# XMOS_TSBOARD_Power.net
KiCad netlist of a schematic drawn in Altium Designer
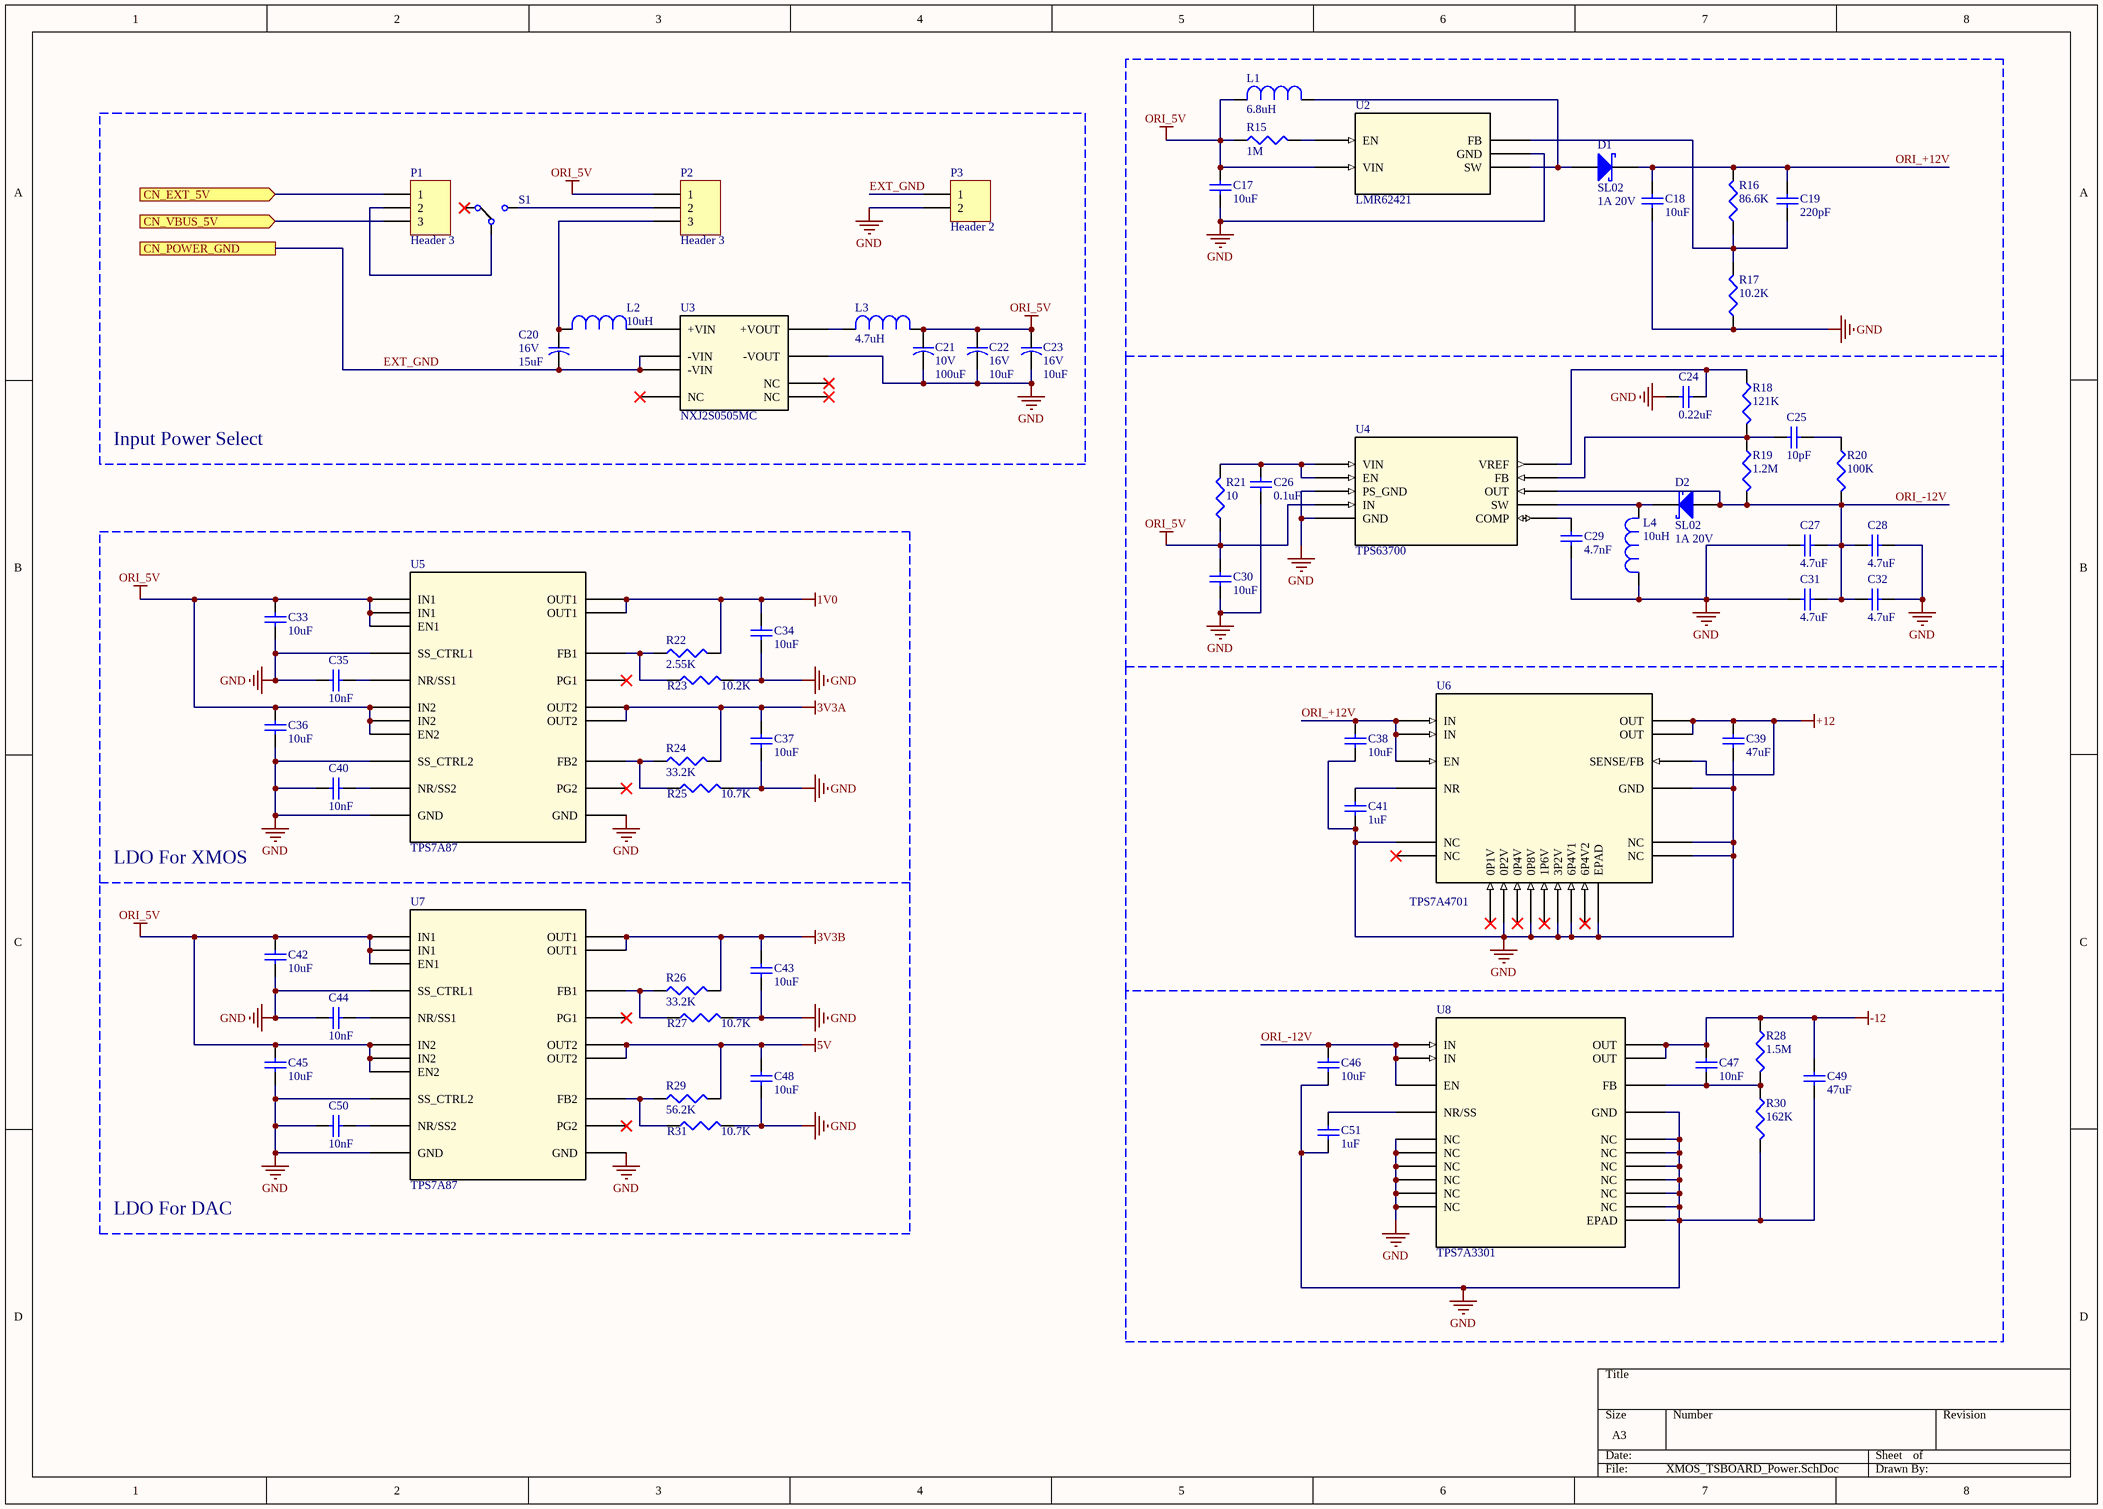
[diagram p0: XMOS_TSBOARD_Power.SchDoc]

(export (version "E")
  (design (tool "Eeschema 10.0.6"))
  (components
    (comp (ref "C17")
      (value "10uF")
      (footprint "1608[0603]")
      (description "Capacitor (Semiconductor SIM Model)")
      (fields (field (name "Comment") "Cap Semi") (field (name "PUBLISHER") "Altium Limited"))
      (libsource (lib "Miscellaneous Devices") (part "Cap Semi"))
    )
    (comp (ref "C18")
      (value "10uF")
      (footprint "C0805")
      (description "Capacitor (Semiconductor SIM Model)")
      (fields (field (name "Comment") "Cap Semi") (field (name "PUBLISHER") "Altium Limited"))
      (libsource (lib "Miscellaneous Devices") (part "Cap Semi"))
    )
    (comp (ref "C19")
      (value "220pF")
      (footprint "1608[0603]")
      (description "Capacitor (Semiconductor SIM Model)")
      (fields (field (name "Comment") "Cap Semi") (field (name "PUBLISHER") "Altium Limited"))
      (libsource (lib "Miscellaneous Devices") (part "Cap Semi"))
    )
    (comp (ref "C20")
      (value "15uF")
      (footprint "3528-21")
      (description "Polymer Electrolytic Capacitors")
      (fields (field (name "RATEDVOLTAGE") "16V") (field (name "Comment") "KO-CAP"))
      (libsource (lib "Troposphere_lib") (part "T520B"))
    )
    (comp (ref "C21")
      (value "100uF")
      (footprint "3528-21")
      (description "Polymer Electrolytic Capacitors")
      (fields (field (name "RATEDVOLTAGE") "10V") (field (name "Comment") "KO-CAP"))
      (libsource (lib "Troposphere_lib") (part "T520B"))
    )
    (comp (ref "C22")
      (value "10uF")
      (footprint "3528-21")
      (description "Polymer Electrolytic Capacitors")
      (fields (field (name "RATEDVOLTAGE") "16V") (field (name "Comment") "KO-CAP"))
      (libsource (lib "Troposphere_lib") (part "T520B"))
    )
    (comp (ref "C23")
      (value "10uF")
      (footprint "3528-21")
      (description "Polymer Electrolytic Capacitors")
      (fields (field (name "RATEDVOLTAGE") "16V") (field (name "Comment") "KO-CAP"))
      (libsource (lib "Troposphere_lib") (part "T520B"))
    )
    (comp (ref "C24")
      (value "0.22uF")
      (footprint "1608[0603]")
      (description "Capacitor (Semiconductor SIM Model)")
      (fields (field (name "Comment") "Cap Semi") (field (name "PUBLISHER") "Altium Limited"))
      (libsource (lib "Miscellaneous Devices") (part "Cap Semi"))
    )
    (comp (ref "C25")
      (value "10pF")
      (footprint "1608[0603]")
      (description "Capacitor (Semiconductor SIM Model)")
      (fields (field (name "Comment") "Cap Semi") (field (name "PUBLISHER") "Altium Limited"))
      (libsource (lib "Miscellaneous Devices") (part "Cap Semi"))
    )
    (comp (ref "C26")
      (value "0.1uF")
      (footprint "1608[0603]")
      (description "Capacitor (Semiconductor SIM Model)")
      (fields (field (name "Comment") "Cap Semi") (field (name "PUBLISHER") "Altium Limited"))
      (libsource (lib "Miscellaneous Devices") (part "Cap Semi"))
    )
    (comp (ref "C27")
      (value "4.7uF")
      (footprint "C0805")
      (description "Capacitor (Semiconductor SIM Model)")
      (fields (field (name "Comment") "Cap Semi") (field (name "PUBLISHER") "Altium Limited"))
      (libsource (lib "Miscellaneous Devices") (part "Cap Semi"))
    )
    (comp (ref "C28")
      (value "4.7uF")
      (footprint "C0805")
      (description "Capacitor (Semiconductor SIM Model)")
      (fields (field (name "Comment") "Cap Semi") (field (name "PUBLISHER") "Altium Limited"))
      (libsource (lib "Miscellaneous Devices") (part "Cap Semi"))
    )
    (comp (ref "C29")
      (value "4.7nF")
      (footprint "1608[0603]")
      (description "Capacitor (Semiconductor SIM Model)")
      (fields (field (name "Comment") "Cap Semi") (field (name "PUBLISHER") "Altium Limited"))
      (libsource (lib "Miscellaneous Devices") (part "Cap Semi"))
    )
    (comp (ref "C30")
      (value "10uF")
      (footprint "1608[0603]")
      (description "Capacitor (Semiconductor SIM Model)")
      (fields (field (name "Comment") "Cap Semi") (field (name "PUBLISHER") "Altium Limited"))
      (libsource (lib "Miscellaneous Devices") (part "Cap Semi"))
    )
    (comp (ref "C31")
      (value "4.7uF")
      (footprint "C0805")
      (description "Capacitor (Semiconductor SIM Model)")
      (fields (field (name "Comment") "Cap Semi") (field (name "PUBLISHER") "Altium Limited"))
      (libsource (lib "Miscellaneous Devices") (part "Cap Semi"))
    )
    (comp (ref "C32")
      (value "4.7uF")
      (footprint "C0805")
      (description "Capacitor (Semiconductor SIM Model)")
      (fields (field (name "Comment") "Cap Semi") (field (name "PUBLISHER") "Altium Limited"))
      (libsource (lib "Miscellaneous Devices") (part "Cap Semi"))
    )
    (comp (ref "C33")
      (value "10uF")
      (footprint "1608[0603]")
      (description "Capacitor (Semiconductor SIM Model)")
      (fields (field (name "Comment") "Cap Semi") (field (name "PUBLISHER") "Altium Limited"))
      (libsource (lib "Miscellaneous Devices") (part "Cap Semi"))
    )
    (comp (ref "C34")
      (value "10uF")
      (footprint "1608[0603]")
      (description "Capacitor (Semiconductor SIM Model)")
      (fields (field (name "Comment") "Cap Semi") (field (name "PUBLISHER") "Altium Limited"))
      (libsource (lib "Miscellaneous Devices") (part "Cap Semi"))
    )
    (comp (ref "C35")
      (value "10nF")
      (footprint "1608[0603]")
      (description "Capacitor (Semiconductor SIM Model)")
      (fields (field (name "Comment") "Cap Semi") (field (name "PUBLISHER") "Altium Limited"))
      (libsource (lib "Miscellaneous Devices") (part "Cap Semi"))
    )
    (comp (ref "C36")
      (value "10uF")
      (footprint "1608[0603]")
      (description "Capacitor (Semiconductor SIM Model)")
      (fields (field (name "Comment") "Cap Semi") (field (name "PUBLISHER") "Altium Limited"))
      (libsource (lib "Miscellaneous Devices") (part "Cap Semi"))
    )
    (comp (ref "C37")
      (value "10uF")
      (footprint "1608[0603]")
      (description "Capacitor (Semiconductor SIM Model)")
      (fields (field (name "Comment") "Cap Semi") (field (name "PUBLISHER") "Altium Limited"))
      (libsource (lib "Miscellaneous Devices") (part "Cap Semi"))
    )
    (comp (ref "C38")
      (value "10uF")
      (footprint "C0805")
      (description "Capacitor (Semiconductor SIM Model)")
      (fields (field (name "Comment") "Cap Semi") (field (name "PUBLISHER") "Altium Limited"))
      (libsource (lib "Miscellaneous Devices") (part "Cap Semi"))
    )
    (comp (ref "C39")
      (value "47uF")
      (footprint "C1210")
      (description "Capacitor (Semiconductor SIM Model)")
      (fields (field (name "Comment") "Cap Semi") (field (name "PUBLISHER") "Altium Limited"))
      (libsource (lib "Miscellaneous Devices") (part "Cap Semi"))
    )
    (comp (ref "C40")
      (value "10nF")
      (footprint "1608[0603]")
      (description "Capacitor (Semiconductor SIM Model)")
      (fields (field (name "Comment") "Cap Semi") (field (name "PUBLISHER") "Altium Limited"))
      (libsource (lib "Miscellaneous Devices") (part "Cap Semi"))
    )
    (comp (ref "C41")
      (value "1uF")
      (footprint "1608[0603]")
      (description "Capacitor (Semiconductor SIM Model)")
      (fields (field (name "Comment") "Cap Semi") (field (name "PUBLISHER") "Altium Limited"))
      (libsource (lib "Miscellaneous Devices") (part "Cap Semi"))
    )
    (comp (ref "C42")
      (value "10uF")
      (footprint "1608[0603]")
      (description "Capacitor (Semiconductor SIM Model)")
      (fields (field (name "Comment") "Cap Semi") (field (name "PUBLISHER") "Altium Limited"))
      (libsource (lib "Miscellaneous Devices") (part "Cap Semi"))
    )
    (comp (ref "C43")
      (value "10uF")
      (footprint "1608[0603]")
      (description "Capacitor (Semiconductor SIM Model)")
      (fields (field (name "Comment") "Cap Semi") (field (name "PUBLISHER") "Altium Limited"))
      (libsource (lib "Miscellaneous Devices") (part "Cap Semi"))
    )
    (comp (ref "C44")
      (value "10nF")
      (footprint "1608[0603]")
      (description "Capacitor (Semiconductor SIM Model)")
      (fields (field (name "Comment") "Cap Semi") (field (name "PUBLISHER") "Altium Limited"))
      (libsource (lib "Miscellaneous Devices") (part "Cap Semi"))
    )
    (comp (ref "C45")
      (value "10uF")
      (footprint "1608[0603]")
      (description "Capacitor (Semiconductor SIM Model)")
      (fields (field (name "Comment") "Cap Semi") (field (name "PUBLISHER") "Altium Limited"))
      (libsource (lib "Miscellaneous Devices") (part "Cap Semi"))
    )
    (comp (ref "C46")
      (value "10uF")
      (footprint "C0805")
      (description "Capacitor (Semiconductor SIM Model)")
      (fields (field (name "Comment") "Cap Semi") (field (name "PUBLISHER") "Altium Limited"))
      (libsource (lib "Miscellaneous Devices") (part "Cap Semi"))
    )
    (comp (ref "C47")
      (value "10nF")
      (footprint "1608[0603]")
      (description "Capacitor (Semiconductor SIM Model)")
      (fields (field (name "Comment") "Cap Semi") (field (name "PUBLISHER") "Altium Limited"))
      (libsource (lib "Miscellaneous Devices") (part "Cap Semi"))
    )
    (comp (ref "C48")
      (value "10uF")
      (footprint "1608[0603]")
      (description "Capacitor (Semiconductor SIM Model)")
      (fields (field (name "Comment") "Cap Semi") (field (name "PUBLISHER") "Altium Limited"))
      (libsource (lib "Miscellaneous Devices") (part "Cap Semi"))
    )
    (comp (ref "C49")
      (value "47uF")
      (footprint "C1210")
      (description "Capacitor (Semiconductor SIM Model)")
      (fields (field (name "Comment") "Cap Semi") (field (name "PUBLISHER") "Altium Limited"))
      (libsource (lib "Miscellaneous Devices") (part "Cap Semi"))
    )
    (comp (ref "C50")
      (value "10nF")
      (footprint "1608[0603]")
      (description "Capacitor (Semiconductor SIM Model)")
      (fields (field (name "Comment") "Cap Semi") (field (name "PUBLISHER") "Altium Limited"))
      (libsource (lib "Miscellaneous Devices") (part "Cap Semi"))
    )
    (comp (ref "C51")
      (value "1uF")
      (footprint "1608[0603]")
      (description "Capacitor (Semiconductor SIM Model)")
      (fields (field (name "Comment") "Cap Semi") (field (name "PUBLISHER") "Altium Limited"))
      (libsource (lib "Miscellaneous Devices") (part "Cap Semi"))
    )
    (comp (ref "D1")
      (value "SL02")
      (footprint "DO-219AB")
      (description "Schottky Rectifier")
      (fields (field (name "ALTIUM_VALUE") "1A 20V"))
      (libsource (lib "Troposphere_lib") (part "SL02"))
    )
    (comp (ref "D2")
      (value "SL02")
      (footprint "DO-219AB")
      (description "Schottky Rectifier")
      (fields (field (name "ALTIUM_VALUE") "1A 20V"))
      (libsource (lib "Troposphere_lib") (part "SL02"))
    )
    (comp (ref "L1")
      (value "6.8uH")
      (footprint "4240")
      (description "Inductors for power circuits, wound metal, SPM series")
      (fields (field (name "Comment") "SPM"))
      (libsource (lib "Troposphere_lib") (part "SPM"))
    )
    (comp (ref "L2")
      (value "10uH")
      (footprint "5250")
      (description "Inductors for power circuits, wound metal, SPM series")
      (fields (field (name "Comment") "SPM"))
      (libsource (lib "Troposphere_lib") (part "SPM"))
    )
    (comp (ref "L3")
      (value "4.7uH")
      (footprint "4240")
      (description "Inductors for power circuits, wound metal, SPM series")
      (fields (field (name "Comment") "SPM"))
      (libsource (lib "Troposphere_lib") (part "SPM"))
    )
    (comp (ref "L4")
      (value "10uH")
      (footprint "4240")
      (description "Inductors for power circuits, wound metal, SPM series")
      (fields (field (name "Comment") "SPM"))
      (libsource (lib "Troposphere_lib") (part "SPM"))
    )
    (comp (ref "P1")
      (value "Header 3")
      (footprint "HDR1X3")
      (description "Header, 3-Pin")
      (fields (field (name "PUBLISHER") "Altium Limited"))
      (libsource (lib "Miscellaneous Connectors") (part "Header 3"))
    )
    (comp (ref "P2")
      (value "Header 3")
      (footprint "HDR1X3")
      (description "Header, 3-Pin")
      (fields (field (name "PUBLISHER") "Altium Limited"))
      (libsource (lib "Miscellaneous Connectors") (part "Header 3"))
    )
    (comp (ref "P3")
      (value "Header 2")
      (footprint "HDR1X2")
      (description "Header, 2-Pin")
      (fields (field (name "PUBLISHER") "Altium Limited"))
      (libsource (lib "Miscellaneous Connectors") (part "Header 2"))
    )
    (comp (ref "R15")
      (value "1M")
      (footprint "J1-0603")
      (description "Resistor")
      (fields (field (name "Comment") "Res3") (field (name "PUBLISHER") "Altium Limited"))
      (libsource (lib "Miscellaneous Devices") (part "Res3"))
    )
    (comp (ref "R16")
      (value "86.6K")
      (footprint "J1-0603")
      (description "Resistor")
      (fields (field (name "Comment") "Res3") (field (name "PUBLISHER") "Altium Limited"))
      (libsource (lib "Miscellaneous Devices") (part "Res3"))
    )
    (comp (ref "R17")
      (value "10.2K")
      (footprint "J1-0603")
      (description "Resistor")
      (fields (field (name "Comment") "Res3") (field (name "PUBLISHER") "Altium Limited"))
      (libsource (lib "Miscellaneous Devices") (part "Res3"))
    )
    (comp (ref "R18")
      (value "121K")
      (footprint "J1-0603")
      (description "Resistor")
      (fields (field (name "Comment") "Res3") (field (name "PUBLISHER") "Altium Limited"))
      (libsource (lib "Miscellaneous Devices") (part "Res3"))
    )
    (comp (ref "R19")
      (value "1.2M")
      (footprint "J1-0603")
      (description "Resistor")
      (fields (field (name "Comment") "Res3") (field (name "PUBLISHER") "Altium Limited"))
      (libsource (lib "Miscellaneous Devices") (part "Res3"))
    )
    (comp (ref "R20")
      (value "100K")
      (footprint "J1-0603")
      (description "Resistor")
      (fields (field (name "Comment") "Res3") (field (name "PUBLISHER") "Altium Limited"))
      (libsource (lib "Miscellaneous Devices") (part "Res3"))
    )
    (comp (ref "R21")
      (value "10")
      (footprint "J1-0603")
      (description "Resistor")
      (fields (field (name "Comment") "Res3") (field (name "PUBLISHER") "Altium Limited"))
      (libsource (lib "Miscellaneous Devices") (part "Res3"))
    )
    (comp (ref "R22")
      (value "2.55K")
      (footprint "J1-0603")
      (description "Resistor")
      (fields (field (name "Comment") "Res3") (field (name "PUBLISHER") "Altium Limited"))
      (libsource (lib "Miscellaneous Devices") (part "Res3"))
    )
    (comp (ref "R23")
      (value "10.2K")
      (footprint "J1-0603")
      (description "Resistor")
      (fields (field (name "Comment") "Res3") (field (name "PUBLISHER") "Altium Limited"))
      (libsource (lib "Miscellaneous Devices") (part "Res3"))
    )
    (comp (ref "R24")
      (value "33.2K")
      (footprint "J1-0603")
      (description "Resistor")
      (fields (field (name "Comment") "Res3") (field (name "PUBLISHER") "Altium Limited"))
      (libsource (lib "Miscellaneous Devices") (part "Res3"))
    )
    (comp (ref "R25")
      (value "10.7K")
      (footprint "J1-0603")
      (description "Resistor")
      (fields (field (name "Comment") "Res3") (field (name "PUBLISHER") "Altium Limited"))
      (libsource (lib "Miscellaneous Devices") (part "Res3"))
    )
    (comp (ref "R26")
      (value "33.2K")
      (footprint "J1-0603")
      (description "Resistor")
      (fields (field (name "Comment") "Res3") (field (name "PUBLISHER") "Altium Limited"))
      (libsource (lib "Miscellaneous Devices") (part "Res3"))
    )
    (comp (ref "R27")
      (value "10.7K")
      (footprint "J1-0603")
      (description "Resistor")
      (fields (field (name "Comment") "Res3") (field (name "PUBLISHER") "Altium Limited"))
      (libsource (lib "Miscellaneous Devices") (part "Res3"))
    )
    (comp (ref "R28")
      (value "1.5M")
      (footprint "J1-0603")
      (description "Resistor")
      (fields (field (name "Comment") "Res3") (field (name "PUBLISHER") "Altium Limited"))
      (libsource (lib "Miscellaneous Devices") (part "Res3"))
    )
    (comp (ref "R29")
      (value "56.2K")
      (footprint "J1-0603")
      (description "Resistor")
      (fields (field (name "Comment") "Res3") (field (name "PUBLISHER") "Altium Limited"))
      (libsource (lib "Miscellaneous Devices") (part "Res3"))
    )
    (comp (ref "R30")
      (value "162K")
      (footprint "J1-0603")
      (description "Resistor")
      (fields (field (name "Comment") "Res3") (field (name "PUBLISHER") "Altium Limited"))
      (libsource (lib "Miscellaneous Devices") (part "Res3"))
    )
    (comp (ref "R31")
      (value "10.7K")
      (footprint "J1-0603")
      (description "Resistor")
      (fields (field (name "Comment") "Res3") (field (name "PUBLISHER") "Altium Limited"))
      (libsource (lib "Miscellaneous Devices") (part "Res3"))
    )
    (comp (ref "S1")
      (value "SSSS213202")
      (footprint "SS_SMD_213202")
      (description "Slide Switch 3.5(H)mm, 2.0mm-travel Type SSSS2 Series")
      (libsource (lib "Troposphere_lib") (part "SSSS213202"))
    )
    (comp (ref "U2")
      (value "LMR62421")
      (footprint "DBV5")
      (description "LMR62421 SIMPLE SWITCHER® 24Vout, 2.1A Step-Up Voltage Regulator in SOT-23")
      (libsource (lib "Troposphere_lib") (part "LMR62421"))
    )
    (comp (ref "U3")
      (value "NXJ2S0505MC")
      (footprint "SMD_NXJ2S0505")
      (description "Isolated 2W Single Output SM DC-DC Converters")
      (libsource (lib "Troposphere_lib") (part "NXJ2S0505MC"))
    )
    (comp (ref "U4")
      (value "TPS63700")
      (footprint "DRC10")
      (description "DC-DC Inverter")
      (libsource (lib "Troposphere_lib") (part "TPS63700"))
    )
    (comp (ref "U5")
      (value "TPS7A87")
      (footprint "RTJ20")
      (description "Dual, 500-mA, Low-Noise (3.8 μVRMS), LDO Voltage Regulator")
      (libsource (lib "Troposphere_lib") (part "TPS7A87"))
    )
    (comp (ref "U6")
      (value "TPS7A4701")
      (footprint "RGW20")
      (description "TPS7A470x 36-V, 1-A, 4-µVRMS, RF LDO Voltage Regulator")
      (libsource (lib "Troposphere_lib") (part "TPS7A4701"))
    )
    (comp (ref "U7")
      (value "TPS7A87")
      (footprint "RTJ20")
      (description "Dual, 500-mA, Low-Noise (3.8 μVRMS), LDO Voltage Regulator")
      (libsource (lib "Troposphere_lib") (part "TPS7A87"))
    )
    (comp (ref "U8")
      (value "TPS7A3301")
      (footprint "RGW20")
      (description "TPS7A33 –36-V, 1-A, Ultralow-Noise Negative Voltage Regulator")
      (libsource (lib "Troposphere_lib") (part "TPS7A3301"))
    )
  )
  (nets
    (net (code "1") (name "+12") (class "Default")
      (node (ref "C39") (pin "2") (pinfunction "2_2") (pintype "passive"))
      (node (ref "U6") (pin "1") (pinfunction "OUT_1") (pintype "power_in"))
      (node (ref "U6") (pin "20") (pinfunction "OUT_20") (pintype "power_in"))
      (node (ref "U6") (pin "3") (pinfunction "SENSE/FB_3") (pintype "input"))
    )
    (net (code "2") (name "-12") (class "Default")
      (node (ref "C47") (pin "1") (pinfunction "1_1") (pintype "passive"))
      (node (ref "C49") (pin "2") (pinfunction "2_2") (pintype "passive"))
      (node (ref "R28") (pin "1") (pinfunction "1_1") (pintype "passive"))
      (node (ref "U8") (pin "1") (pinfunction "OUT_1") (pintype "power_in"))
      (node (ref "U8") (pin "20") (pinfunction "OUT_20") (pintype "power_in"))
    )
    (net (code "3") (name "/CN_EXT_5V") (class "Default")
      (node (ref "P1") (pin "1") (pinfunction "1_1") (pintype "passive"))
    )
    (net (code "4") (name "/CN_VBUS_5V") (class "Default")
      (node (ref "P1") (pin "3") (pinfunction "3_3") (pintype "passive"))
    )
    (net (code "5") (name "/EXT_GND") (class "Default")
      (node (ref "C20") (pin "2") (pinfunction "2_2") (pintype "passive"))
      (node (ref "P3") (pin "1") (pinfunction "1_1") (pintype "passive"))
      (node (ref "U3") (pin "11") (pinfunction "-VIN_11") (pintype "power_in"))
      (node (ref "U3") (pin "2") (pinfunction "-VIN_2") (pintype "power_in"))
    )
    (net (code "6") (name "/ORI_+12V") (class "Default")
      (node (ref "C18") (pin "2") (pinfunction "2_2") (pintype "passive"))
      (node (ref "C19") (pin "2") (pinfunction "2_2") (pintype "passive"))
      (node (ref "C38") (pin "2") (pinfunction "2_2") (pintype "passive"))
      (node (ref "D1") (pin "2") (pinfunction "2_2") (pintype "power_in"))
      (node (ref "R16") (pin "2") (pinfunction "2_2") (pintype "passive"))
      (node (ref "U6") (pin "13") (pinfunction "EN_13") (pintype "input"))
      (node (ref "U6") (pin "15") (pinfunction "IN_15") (pintype "input"))
      (node (ref "U6") (pin "16") (pinfunction "IN_16") (pintype "input"))
    )
    (net (code "7") (name "/ORI_-12V") (class "Default")
      (node (ref "C27") (pin "1") (pinfunction "1_1") (pintype "passive"))
      (node (ref "C28") (pin "2") (pinfunction "2_2") (pintype "passive"))
      (node (ref "C31") (pin "1") (pinfunction "1_1") (pintype "passive"))
      (node (ref "C32") (pin "2") (pinfunction "2_2") (pintype "passive"))
      (node (ref "C46") (pin "2") (pinfunction "2_2") (pintype "passive"))
      (node (ref "D2") (pin "1") (pinfunction "1_1") (pintype "power_in"))
      (node (ref "R19") (pin "2") (pinfunction "2_2") (pintype "passive"))
      (node (ref "R20") (pin "2") (pinfunction "2_2") (pintype "passive"))
      (node (ref "U4") (pin "8") (pinfunction "OUT_8") (pintype "input"))
      (node (ref "U8") (pin "13") (pinfunction "EN_13") (pintype "passive"))
      (node (ref "U8") (pin "15") (pinfunction "IN_15") (pintype "input"))
      (node (ref "U8") (pin "16") (pinfunction "IN_16") (pintype "input"))
    )
    (net (code "8") (name "1V0") (class "Default")
      (node (ref "C34") (pin "2") (pinfunction "2_2") (pintype "passive"))
      (node (ref "R22") (pin "2") (pinfunction "2_2") (pintype "passive"))
      (node (ref "U5") (pin "14") (pinfunction "OUT1_14") (pintype "power_in"))
      (node (ref "U5") (pin "15") (pinfunction "OUT1_15") (pintype "power_in"))
    )
    (net (code "9") (name "3V3A") (class "Default")
      (node (ref "C37") (pin "2") (pinfunction "2_2") (pintype "passive"))
      (node (ref "R24") (pin "2") (pinfunction "2_2") (pintype "passive"))
      (node (ref "U5") (pin "11") (pinfunction "OUT2_11") (pintype "power_in"))
      (node (ref "U5") (pin "12") (pinfunction "OUT2_12") (pintype "power_in"))
    )
    (net (code "10") (name "3V3B") (class "Default")
      (node (ref "C43") (pin "2") (pinfunction "2_2") (pintype "passive"))
      (node (ref "R26") (pin "2") (pinfunction "2_2") (pintype "passive"))
      (node (ref "U7") (pin "14") (pinfunction "OUT1_14") (pintype "power_in"))
      (node (ref "U7") (pin "15") (pinfunction "OUT1_15") (pintype "power_in"))
    )
    (net (code "11") (name "5V") (class "Default")
      (node (ref "C48") (pin "2") (pinfunction "2_2") (pintype "passive"))
      (node (ref "R29") (pin "2") (pinfunction "2_2") (pintype "passive"))
      (node (ref "U7") (pin "11") (pinfunction "OUT2_11") (pintype "power_in"))
      (node (ref "U7") (pin "12") (pinfunction "OUT2_12") (pintype "power_in"))
    )
    (net (code "12") (name "GND") (class "Default")
      (node (ref "C17") (pin "1") (pinfunction "1_1") (pintype "passive"))
      (node (ref "C18") (pin "1") (pinfunction "1_1") (pintype "passive"))
      (node (ref "C21") (pin "2") (pinfunction "2_2") (pintype "passive"))
      (node (ref "C22") (pin "2") (pinfunction "2_2") (pintype "passive"))
      (node (ref "C23") (pin "2") (pinfunction "2_2") (pintype "passive"))
      (node (ref "C24") (pin "2") (pinfunction "2_2") (pintype "passive"))
      (node (ref "C26") (pin "1") (pinfunction "1_1") (pintype "passive"))
      (node (ref "C27") (pin "2") (pinfunction "2_2") (pintype "passive"))
      (node (ref "C28") (pin "1") (pinfunction "1_1") (pintype "passive"))
      (node (ref "C29") (pin "2") (pinfunction "2_2") (pintype "passive"))
      (node (ref "C30") (pin "1") (pinfunction "1_1") (pintype "passive"))
      (node (ref "C31") (pin "2") (pinfunction "2_2") (pintype "passive"))
      (node (ref "C32") (pin "1") (pinfunction "1_1") (pintype "passive"))
      (node (ref "C33") (pin "1") (pinfunction "1_1") (pintype "passive"))
      (node (ref "C34") (pin "1") (pinfunction "1_1") (pintype "passive"))
      (node (ref "C35") (pin "1") (pinfunction "1_1") (pintype "passive"))
      (node (ref "C36") (pin "1") (pinfunction "1_1") (pintype "passive"))
      (node (ref "C37") (pin "1") (pinfunction "1_1") (pintype "passive"))
      (node (ref "C38") (pin "1") (pinfunction "1_1") (pintype "passive"))
      (node (ref "C39") (pin "1") (pinfunction "1_1") (pintype "passive"))
      (node (ref "C40") (pin "1") (pinfunction "1_1") (pintype "passive"))
      (node (ref "C41") (pin "1") (pinfunction "1_1") (pintype "passive"))
      (node (ref "C42") (pin "1") (pinfunction "1_1") (pintype "passive"))
      (node (ref "C43") (pin "1") (pinfunction "1_1") (pintype "passive"))
      (node (ref "C44") (pin "1") (pinfunction "1_1") (pintype "passive"))
      (node (ref "C45") (pin "1") (pinfunction "1_1") (pintype "passive"))
      (node (ref "C46") (pin "1") (pinfunction "1_1") (pintype "passive"))
      (node (ref "C48") (pin "1") (pinfunction "1_1") (pintype "passive"))
      (node (ref "C49") (pin "1") (pinfunction "1_1") (pintype "passive"))
      (node (ref "C50") (pin "1") (pinfunction "1_1") (pintype "passive"))
      (node (ref "C51") (pin "1") (pinfunction "1_1") (pintype "passive"))
      (node (ref "L4") (pin "2") (pinfunction "2_2") (pintype "passive"))
      (node (ref "P3") (pin "2") (pinfunction "2_2") (pintype "passive"))
      (node (ref "R17") (pin "1") (pinfunction "1_1") (pintype "passive"))
      (node (ref "R23") (pin "2") (pinfunction "2_2") (pintype "passive"))
      (node (ref "R25") (pin "2") (pinfunction "2_2") (pintype "passive"))
      (node (ref "R27") (pin "2") (pinfunction "2_2") (pintype "passive"))
      (node (ref "R30") (pin "2") (pinfunction "2_2") (pintype "passive"))
      (node (ref "R31") (pin "2") (pinfunction "2_2") (pintype "passive"))
      (node (ref "U2") (pin "2") (pinfunction "GND_2") (pintype "power_in"))
      (node (ref "U3") (pin "5") (pinfunction "-VOUT_5") (pintype "power_in"))
      (node (ref "U4") (pin "2") (pinfunction "GND_2") (pintype "power_in"))
      (node (ref "U4") (pin "7") (pinfunction "PS_GND_7") (pintype "input"))
      (node (ref "U5") (pin "13") (pinfunction "GND_13") (pintype "power_in"))
      (node (ref "U5") (pin "18") (pinfunction "SS_CTRL1_18") (pintype "power_in"))
      (node (ref "U5") (pin "3") (pinfunction "GND_3") (pintype "power_in"))
      (node (ref "U5") (pin "8") (pinfunction "SS_CTRL2_8") (pintype "power_in"))
      (node (ref "U6") (pin "11") (pinfunction "0P2V_11") (pintype "input"))
      (node (ref "U6") (pin "17") (pinfunction "NC_17") (pintype "passive"))
      (node (ref "U6") (pin "18") (pinfunction "NC_18") (pintype "passive"))
      (node (ref "U6") (pin "19") (pinfunction "NC_19") (pintype "passive"))
      (node (ref "U6") (pin "21") (pinfunction "EPAD_21") (pintype "passive"))
      (node (ref "U6") (pin "5") (pinfunction "6P4V1_5") (pintype "input"))
      (node (ref "U6") (pin "6") (pinfunction "3P2V_6") (pintype "input"))
      (node (ref "U6") (pin "7") (pinfunction "GND_7") (pintype "power_in"))
      (node (ref "U6") (pin "9") (pinfunction "0P8V_9") (pintype "input"))
      (node (ref "U7") (pin "13") (pinfunction "GND_13") (pintype "power_in"))
      (node (ref "U7") (pin "18") (pinfunction "SS_CTRL1_18") (pintype "power_in"))
      (node (ref "U7") (pin "3") (pinfunction "GND_3") (pintype "power_in"))
      (node (ref "U7") (pin "8") (pinfunction "SS_CTRL2_8") (pintype "power_in"))
      (node (ref "U8") (pin "10") (pinfunction "NC_10") (pintype "passive"))
      (node (ref "U8") (pin "11") (pinfunction "NC_11") (pintype "passive"))
      (node (ref "U8") (pin "12") (pinfunction "NC_12") (pintype "passive"))
      (node (ref "U8") (pin "17") (pinfunction "NC_17") (pintype "passive"))
      (node (ref "U8") (pin "18") (pinfunction "NC_18") (pintype "passive"))
      (node (ref "U8") (pin "19") (pinfunction "NC_19") (pintype "passive"))
      (node (ref "U8") (pin "2") (pinfunction "NC_2") (pintype "passive"))
      (node (ref "U8") (pin "21") (pinfunction "EPAD_21") (pintype "passive"))
      (node (ref "U8") (pin "4") (pinfunction "NC_4") (pintype "passive"))
      (node (ref "U8") (pin "5") (pinfunction "NC_5") (pintype "passive"))
      (node (ref "U8") (pin "6") (pinfunction "NC_6") (pintype "passive"))
      (node (ref "U8") (pin "7") (pinfunction "GND_7") (pintype "power_in"))
      (node (ref "U8") (pin "8") (pinfunction "NC_8") (pintype "passive"))
      (node (ref "U8") (pin "9") (pinfunction "NC_9") (pintype "passive"))
    )
    (net (code "13") (name "Net-(C20-Pad1)") (class "Default")
      (node (ref "C20") (pin "1") (pinfunction "1_1") (pintype "passive"))
      (node (ref "L2") (pin "2") (pinfunction "2_2") (pintype "passive"))
      (node (ref "P2") (pin "3") (pinfunction "3_3") (pintype "passive"))
    )
    (net (code "14") (name "Net-(C25-Pad1)") (class "Default")
      (node (ref "C25") (pin "1") (pinfunction "1_1") (pintype "passive"))
      (node (ref "R20") (pin "1") (pinfunction "1_1") (pintype "passive"))
    )
    (net (code "15") (name "Net-(P2-Pad2)") (class "Default")
      (node (ref "P2") (pin "2") (pinfunction "2_2") (pintype "passive"))
      (node (ref "S1") (pin "3") (pinfunction "3_3") (pintype "power_in"))
    )
    (net (code "16") (name "Net-(S1-COM)") (class "Default")
      (node (ref "P1") (pin "2") (pinfunction "2_2") (pintype "passive"))
      (node (ref "S1") (pin "2") (pinfunction "COM_2") (pintype "power_in"))
    )
    (net (code "17") (name "Net-(U2-EN)") (class "Default")
      (node (ref "R15") (pin "2") (pinfunction "2_2") (pintype "passive"))
      (node (ref "U2") (pin "4") (pinfunction "EN_4") (pintype "input"))
    )
    (net (code "18") (name "Net-(U2-FB)") (class "Default")
      (node (ref "C19") (pin "1") (pinfunction "1_1") (pintype "passive"))
      (node (ref "R16") (pin "1") (pinfunction "1_1") (pintype "passive"))
      (node (ref "R17") (pin "2") (pinfunction "2_2") (pintype "passive"))
      (node (ref "U2") (pin "3") (pinfunction "FB_3") (pintype "passive"))
    )
    (net (code "19") (name "Net-(U2-SW)") (class "Default")
      (node (ref "D1") (pin "1") (pinfunction "1_1") (pintype "power_in"))
      (node (ref "L1") (pin "1") (pinfunction "1_1") (pintype "passive"))
      (node (ref "U2") (pin "1") (pinfunction "SW_1") (pintype "power_in"))
    )
    (net (code "20") (name "Net-(U3-+VIN)") (class "Default")
      (node (ref "L2") (pin "1") (pinfunction "1_1") (pintype "passive"))
      (node (ref "U3") (pin "1") (pinfunction "+VIN_1") (pintype "power_in"))
    )
    (net (code "21") (name "Net-(U3-+VOUT)") (class "Default")
      (node (ref "L3") (pin "2") (pinfunction "2_2") (pintype "passive"))
      (node (ref "U3") (pin "6") (pinfunction "+VOUT_6") (pintype "power_in"))
    )
    (net (code "22") (name "Net-(U4-COMP)") (class "Default")
      (node (ref "C29") (pin "1") (pinfunction "1_1") (pintype "passive"))
      (node (ref "U4") (pin "1") (pinfunction "COMP_1") (pintype "bidirectional"))
    )
    (net (code "23") (name "Net-(U4-EN)") (class "Default")
      (node (ref "C26") (pin "2") (pinfunction "2_2") (pintype "passive"))
      (node (ref "R21") (pin "2") (pinfunction "2_2") (pintype "passive"))
      (node (ref "U4") (pin "3") (pinfunction "VIN_3") (pintype "input"))
      (node (ref "U4") (pin "4") (pinfunction "EN_4") (pintype "input"))
    )
    (net (code "24") (name "Net-(U4-FB)") (class "Default")
      (node (ref "C25") (pin "2") (pinfunction "2_2") (pintype "passive"))
      (node (ref "R18") (pin "2") (pinfunction "2_2") (pintype "passive"))
      (node (ref "R19") (pin "1") (pinfunction "1_1") (pintype "passive"))
      (node (ref "U4") (pin "9") (pinfunction "FB_9") (pintype "input"))
    )
    (net (code "25") (name "Net-(U4-SW)") (class "Default")
      (node (ref "D2") (pin "2") (pinfunction "2_2") (pintype "power_in"))
      (node (ref "L4") (pin "1") (pinfunction "1_1") (pintype "passive"))
      (node (ref "U4") (pin "6") (pinfunction "SW_6") (pintype "power_in"))
    )
    (net (code "26") (name "Net-(U4-VREF)") (class "Default")
      (node (ref "C24") (pin "1") (pinfunction "1_1") (pintype "passive"))
      (node (ref "R18") (pin "1") (pinfunction "1_1") (pintype "passive"))
      (node (ref "U4") (pin "10") (pinfunction "VREF_10") (pintype "output"))
    )
    (net (code "27") (name "Net-(U5-FB1)") (class "Default")
      (node (ref "R22") (pin "1") (pinfunction "1_1") (pintype "passive"))
      (node (ref "R23") (pin "1") (pinfunction "1_1") (pintype "passive"))
      (node (ref "U5") (pin "16") (pinfunction "FB1_16") (pintype "power_in"))
    )
    (net (code "28") (name "Net-(U5-FB2)") (class "Default")
      (node (ref "R24") (pin "1") (pinfunction "1_1") (pintype "passive"))
      (node (ref "R25") (pin "1") (pinfunction "1_1") (pintype "passive"))
      (node (ref "U5") (pin "10") (pinfunction "FB2_10") (pintype "power_in"))
    )
    (net (code "29") (name "Net-(U5-NR{slash}SS1)") (class "Default")
      (node (ref "C35") (pin "2") (pinfunction "2_2") (pintype "passive"))
      (node (ref "U5") (pin "19") (pinfunction "NR/SS1_19") (pintype "power_in"))
    )
    (net (code "30") (name "Net-(U5-NR{slash}SS2)") (class "Default")
      (node (ref "C40") (pin "2") (pinfunction "2_2") (pintype "passive"))
      (node (ref "U5") (pin "7") (pinfunction "NR/SS2_7") (pintype "power_in"))
    )
    (net (code "31") (name "Net-(U6-NR)") (class "Default")
      (node (ref "C41") (pin "2") (pinfunction "2_2") (pintype "passive"))
      (node (ref "U6") (pin "14") (pinfunction "NR_14") (pintype "passive"))
    )
    (net (code "32") (name "Net-(U7-FB1)") (class "Default")
      (node (ref "R26") (pin "1") (pinfunction "1_1") (pintype "passive"))
      (node (ref "R27") (pin "1") (pinfunction "1_1") (pintype "passive"))
      (node (ref "U7") (pin "16") (pinfunction "FB1_16") (pintype "power_in"))
    )
    (net (code "33") (name "Net-(U7-FB2)") (class "Default")
      (node (ref "R29") (pin "1") (pinfunction "1_1") (pintype "passive"))
      (node (ref "R31") (pin "1") (pinfunction "1_1") (pintype "passive"))
      (node (ref "U7") (pin "10") (pinfunction "FB2_10") (pintype "power_in"))
    )
    (net (code "34") (name "Net-(U7-NR{slash}SS1)") (class "Default")
      (node (ref "C44") (pin "2") (pinfunction "2_2") (pintype "passive"))
      (node (ref "U7") (pin "19") (pinfunction "NR/SS1_19") (pintype "power_in"))
    )
    (net (code "35") (name "Net-(U7-NR{slash}SS2)") (class "Default")
      (node (ref "C50") (pin "2") (pinfunction "2_2") (pintype "passive"))
      (node (ref "U7") (pin "7") (pinfunction "NR/SS2_7") (pintype "power_in"))
    )
    (net (code "36") (name "Net-(U8-FB)") (class "Default")
      (node (ref "C47") (pin "2") (pinfunction "2_2") (pintype "passive"))
      (node (ref "R28") (pin "2") (pinfunction "2_2") (pintype "passive"))
      (node (ref "R30") (pin "1") (pinfunction "1_1") (pintype "passive"))
      (node (ref "U8") (pin "3") (pinfunction "FB_3") (pintype "passive"))
    )
    (net (code "37") (name "Net-(U8-NR{slash}SS)") (class "Default")
      (node (ref "C51") (pin "2") (pinfunction "2_2") (pintype "passive"))
      (node (ref "U8") (pin "14") (pinfunction "NR/SS_14") (pintype "passive"))
    )
    (net (code "38") (name "ORI_5V") (class "Default")
      (node (ref "C17") (pin "2") (pinfunction "2_2") (pintype "passive"))
      (node (ref "C21") (pin "1") (pinfunction "1_1") (pintype "passive"))
      (node (ref "C22") (pin "1") (pinfunction "1_1") (pintype "passive"))
      (node (ref "C23") (pin "1") (pinfunction "1_1") (pintype "passive"))
      (node (ref "C30") (pin "2") (pinfunction "2_2") (pintype "passive"))
      (node (ref "C33") (pin "2") (pinfunction "2_2") (pintype "passive"))
      (node (ref "C36") (pin "2") (pinfunction "2_2") (pintype "passive"))
      (node (ref "C42") (pin "2") (pinfunction "2_2") (pintype "passive"))
      (node (ref "C45") (pin "2") (pinfunction "2_2") (pintype "passive"))
      (node (ref "L1") (pin "2") (pinfunction "2_2") (pintype "passive"))
      (node (ref "L3") (pin "1") (pinfunction "1_1") (pintype "passive"))
      (node (ref "P2") (pin "1") (pinfunction "1_1") (pintype "passive"))
      (node (ref "R15") (pin "1") (pinfunction "1_1") (pintype "passive"))
      (node (ref "R21") (pin "1") (pinfunction "1_1") (pintype "passive"))
      (node (ref "U2") (pin "5") (pinfunction "VIN_5") (pintype "input"))
      (node (ref "U4") (pin "5") (pinfunction "IN_5") (pintype "input"))
      (node (ref "U5") (pin "1") (pinfunction "IN1_1") (pintype "power_in"))
      (node (ref "U5") (pin "2") (pinfunction "IN1_2") (pintype "power_in"))
      (node (ref "U5") (pin "20") (pinfunction "EN1_20") (pintype "power_in"))
      (node (ref "U5") (pin "4") (pinfunction "IN2_4") (pintype "power_in"))
      (node (ref "U5") (pin "5") (pinfunction "IN2_5") (pintype "power_in"))
      (node (ref "U5") (pin "6") (pinfunction "EN2_6") (pintype "power_in"))
      (node (ref "U7") (pin "1") (pinfunction "IN1_1") (pintype "power_in"))
      (node (ref "U7") (pin "2") (pinfunction "IN1_2") (pintype "power_in"))
      (node (ref "U7") (pin "20") (pinfunction "EN1_20") (pintype "power_in"))
      (node (ref "U7") (pin "4") (pinfunction "IN2_4") (pintype "power_in"))
      (node (ref "U7") (pin "5") (pinfunction "IN2_5") (pintype "power_in"))
      (node (ref "U7") (pin "6") (pinfunction "EN2_6") (pintype "power_in"))
    )
    (net (code "39") (name "unconnected-(S1-Pad1)") (class "Default")
      (node (ref "S1") (pin "1") (pinfunction "1_1") (pintype "power_in+no_connect"))
    )
    (net (code "40") (name "unconnected-(U3-NC-Pad7)") (class "Default")
      (node (ref "U3") (pin "7") (pinfunction "NC_7") (pintype "power_in+no_connect"))
    )
    (net (code "41") (name "unconnected-(U3-NC-Pad8)") (class "Default")
      (node (ref "U3") (pin "8") (pinfunction "NC_8") (pintype "power_in+no_connect"))
    )
    (net (code "42") (name "unconnected-(U3-NC-Pad12)") (class "Default")
      (node (ref "U3") (pin "12") (pinfunction "NC_12") (pintype "power_in+no_connect"))
    )
    (net (code "43") (name "unconnected-(U5-PG1-Pad17)") (class "Default")
      (node (ref "U5") (pin "17") (pinfunction "PG1_17") (pintype "power_in+no_connect"))
    )
    (net (code "44") (name "unconnected-(U5-PG2-Pad9)") (class "Default")
      (node (ref "U5") (pin "9") (pinfunction "PG2_9") (pintype "power_in+no_connect"))
    )
    (net (code "45") (name "unconnected-(U6-0P1V-Pad12)") (class "Default")
      (node (ref "U6") (pin "12") (pinfunction "0P1V_12") (pintype "input+no_connect"))
    )
    (net (code "46") (name "unconnected-(U6-0P4V-Pad10)") (class "Default")
      (node (ref "U6") (pin "10") (pinfunction "0P4V_10") (pintype "input+no_connect"))
    )
    (net (code "47") (name "unconnected-(U6-1P6V-Pad8)") (class "Default")
      (node (ref "U6") (pin "8") (pinfunction "1P6V_8") (pintype "input+no_connect"))
    )
    (net (code "48") (name "unconnected-(U6-6P4V2-Pad4)") (class "Default")
      (node (ref "U6") (pin "4") (pinfunction "6P4V2_4") (pintype "input+no_connect"))
    )
    (net (code "49") (name "unconnected-(U6-NC-Pad2)") (class "Default")
      (node (ref "U6") (pin "2") (pinfunction "NC_2") (pintype "passive+no_connect"))
    )
    (net (code "50") (name "unconnected-(U7-PG1-Pad17)") (class "Default")
      (node (ref "U7") (pin "17") (pinfunction "PG1_17") (pintype "power_in+no_connect"))
    )
    (net (code "51") (name "unconnected-(U7-PG2-Pad9)") (class "Default")
      (node (ref "U7") (pin "9") (pinfunction "PG2_9") (pintype "power_in+no_connect"))
    )
  )
)
